# ResistorPatch1.net
KiCad netlist of a schematic drawn in Altium Designer
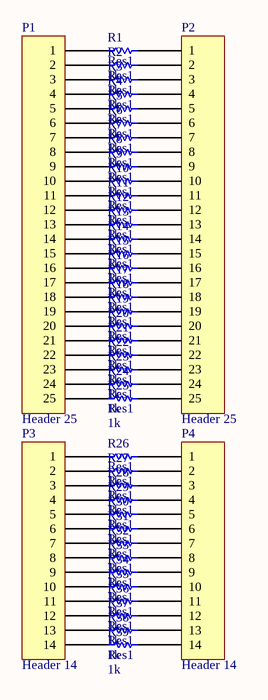
[diagram p0: ResistorPatch1.SchDoc]

(export (version "E")
  (design (tool "Eeschema 10.0.6"))
  (components
    (comp (ref "P1")
      (value "Header 25")
      (footprint "HDR1X25")
      (description "Header, 25-Pin")
      (fields (field (name "PUBLISHER") "Altium Limited"))
      (libsource (lib "") (part "Header 25_1"))
    )
    (comp (ref "P2")
      (value "Header 25")
      (footprint "HDR1X25H")
      (description "Header, 25-Pin")
      (fields (field (name "PUBLISHER") "Altium Limited"))
      (libsource (lib "Miscellaneous Connectors") (part "Header 25"))
    )
    (comp (ref "P3")
      (value "Header 14")
      (footprint "HDR1X14")
      (description "Header, 14-Pin")
      (fields (field (name "PUBLISHER") "Altium Limited"))
      (libsource (lib "") (part "Header 14_1"))
    )
    (comp (ref "P4")
      (value "Header 14")
      (footprint "HDR1X14H")
      (description "Header, 14-Pin")
      (fields (field (name "PUBLISHER") "Altium Limited"))
      (libsource (lib "Miscellaneous Connectors") (part "Header 14"))
    )
    (comp (ref "R1")
      (value "Res1")
      (footprint "AXIAL-0.4")
      (description "Resistor")
      (fields (field (name "ALTIUM_VALUE") "1k") (field (name "PUBLISHER") "Altium Limited"))
      (libsource (lib "Miscellaneous Devices") (part "Res1"))
    )
    (comp (ref "R2")
      (value "Res1")
      (footprint "AXIAL-0.4")
      (description "Resistor")
      (fields (field (name "ALTIUM_VALUE") "1k") (field (name "PUBLISHER") "Altium Limited"))
      (libsource (lib "Miscellaneous Devices") (part "Res1"))
    )
    (comp (ref "R3")
      (value "Res1")
      (footprint "AXIAL-0.4")
      (description "Resistor")
      (fields (field (name "ALTIUM_VALUE") "1k") (field (name "PUBLISHER") "Altium Limited"))
      (libsource (lib "Miscellaneous Devices") (part "Res1"))
    )
    (comp (ref "R4")
      (value "Res1")
      (footprint "AXIAL-0.4")
      (description "Resistor")
      (fields (field (name "ALTIUM_VALUE") "1k") (field (name "PUBLISHER") "Altium Limited"))
      (libsource (lib "Miscellaneous Devices") (part "Res1"))
    )
    (comp (ref "R5")
      (value "Res1")
      (footprint "AXIAL-0.4")
      (description "Resistor")
      (fields (field (name "ALTIUM_VALUE") "1k") (field (name "PUBLISHER") "Altium Limited"))
      (libsource (lib "Miscellaneous Devices") (part "Res1"))
    )
    (comp (ref "R6")
      (value "Res1")
      (footprint "AXIAL-0.4")
      (description "Resistor")
      (fields (field (name "ALTIUM_VALUE") "1k") (field (name "PUBLISHER") "Altium Limited"))
      (libsource (lib "Miscellaneous Devices") (part "Res1"))
    )
    (comp (ref "R7")
      (value "Res1")
      (footprint "AXIAL-0.4")
      (description "Resistor")
      (fields (field (name "ALTIUM_VALUE") "1k") (field (name "PUBLISHER") "Altium Limited"))
      (libsource (lib "Miscellaneous Devices") (part "Res1"))
    )
    (comp (ref "R8")
      (value "Res1")
      (footprint "AXIAL-0.4")
      (description "Resistor")
      (fields (field (name "ALTIUM_VALUE") "1k") (field (name "PUBLISHER") "Altium Limited"))
      (libsource (lib "Miscellaneous Devices") (part "Res1"))
    )
    (comp (ref "R9")
      (value "Res1")
      (footprint "AXIAL-0.4")
      (description "Resistor")
      (fields (field (name "ALTIUM_VALUE") "1k") (field (name "PUBLISHER") "Altium Limited"))
      (libsource (lib "Miscellaneous Devices") (part "Res1"))
    )
    (comp (ref "R10")
      (value "Res1")
      (footprint "AXIAL-0.4")
      (description "Resistor")
      (fields (field (name "ALTIUM_VALUE") "1k") (field (name "PUBLISHER") "Altium Limited"))
      (libsource (lib "Miscellaneous Devices") (part "Res1"))
    )
    (comp (ref "R11")
      (value "Res1")
      (footprint "AXIAL-0.4")
      (description "Resistor")
      (fields (field (name "ALTIUM_VALUE") "1k") (field (name "PUBLISHER") "Altium Limited"))
      (libsource (lib "Miscellaneous Devices") (part "Res1"))
    )
    (comp (ref "R12")
      (value "Res1")
      (footprint "AXIAL-0.4")
      (description "Resistor")
      (fields (field (name "ALTIUM_VALUE") "1k") (field (name "PUBLISHER") "Altium Limited"))
      (libsource (lib "Miscellaneous Devices") (part "Res1"))
    )
    (comp (ref "R13")
      (value "Res1")
      (footprint "AXIAL-0.4")
      (description "Resistor")
      (fields (field (name "ALTIUM_VALUE") "1k") (field (name "PUBLISHER") "Altium Limited"))
      (libsource (lib "Miscellaneous Devices") (part "Res1"))
    )
    (comp (ref "R14")
      (value "Res1")
      (footprint "AXIAL-0.4")
      (description "Resistor")
      (fields (field (name "ALTIUM_VALUE") "1k") (field (name "PUBLISHER") "Altium Limited"))
      (libsource (lib "Miscellaneous Devices") (part "Res1"))
    )
    (comp (ref "R15")
      (value "Res1")
      (footprint "AXIAL-0.4")
      (description "Resistor")
      (fields (field (name "ALTIUM_VALUE") "1k") (field (name "PUBLISHER") "Altium Limited"))
      (libsource (lib "Miscellaneous Devices") (part "Res1"))
    )
    (comp (ref "R16")
      (value "Res1")
      (footprint "AXIAL-0.4")
      (description "Resistor")
      (fields (field (name "ALTIUM_VALUE") "1k") (field (name "PUBLISHER") "Altium Limited"))
      (libsource (lib "Miscellaneous Devices") (part "Res1"))
    )
    (comp (ref "R17")
      (value "Res1")
      (footprint "AXIAL-0.4")
      (description "Resistor")
      (fields (field (name "ALTIUM_VALUE") "1k") (field (name "PUBLISHER") "Altium Limited"))
      (libsource (lib "Miscellaneous Devices") (part "Res1"))
    )
    (comp (ref "R18")
      (value "Res1")
      (footprint "AXIAL-0.4")
      (description "Resistor")
      (fields (field (name "ALTIUM_VALUE") "1k") (field (name "PUBLISHER") "Altium Limited"))
      (libsource (lib "Miscellaneous Devices") (part "Res1"))
    )
    (comp (ref "R19")
      (value "Res1")
      (footprint "AXIAL-0.4")
      (description "Resistor")
      (fields (field (name "ALTIUM_VALUE") "1k") (field (name "PUBLISHER") "Altium Limited"))
      (libsource (lib "Miscellaneous Devices") (part "Res1"))
    )
    (comp (ref "R20")
      (value "Res1")
      (footprint "AXIAL-0.4")
      (description "Resistor")
      (fields (field (name "ALTIUM_VALUE") "1k") (field (name "PUBLISHER") "Altium Limited"))
      (libsource (lib "Miscellaneous Devices") (part "Res1"))
    )
    (comp (ref "R21")
      (value "Res1")
      (footprint "AXIAL-0.4")
      (description "Resistor")
      (fields (field (name "ALTIUM_VALUE") "1k") (field (name "PUBLISHER") "Altium Limited"))
      (libsource (lib "Miscellaneous Devices") (part "Res1"))
    )
    (comp (ref "R22")
      (value "Res1")
      (footprint "AXIAL-0.4")
      (description "Resistor")
      (fields (field (name "ALTIUM_VALUE") "1k") (field (name "PUBLISHER") "Altium Limited"))
      (libsource (lib "Miscellaneous Devices") (part "Res1"))
    )
    (comp (ref "R23")
      (value "Res1")
      (footprint "AXIAL-0.4")
      (description "Resistor")
      (fields (field (name "ALTIUM_VALUE") "1k") (field (name "PUBLISHER") "Altium Limited"))
      (libsource (lib "Miscellaneous Devices") (part "Res1"))
    )
    (comp (ref "R24")
      (value "Res1")
      (footprint "AXIAL-0.4")
      (description "Resistor")
      (fields (field (name "ALTIUM_VALUE") "1k") (field (name "PUBLISHER") "Altium Limited"))
      (libsource (lib "Miscellaneous Devices") (part "Res1"))
    )
    (comp (ref "R25")
      (value "Res1")
      (footprint "AXIAL-0.4")
      (description "Resistor")
      (fields (field (name "ALTIUM_VALUE") "1k") (field (name "PUBLISHER") "Altium Limited"))
      (libsource (lib "Miscellaneous Devices") (part "Res1"))
    )
    (comp (ref "R26")
      (value "Res1")
      (footprint "AXIAL-0.4")
      (description "Resistor")
      (fields (field (name "ALTIUM_VALUE") "1k") (field (name "PUBLISHER") "Altium Limited"))
      (libsource (lib "Miscellaneous Devices") (part "Res1"))
    )
    (comp (ref "R27")
      (value "Res1")
      (footprint "AXIAL-0.4")
      (description "Resistor")
      (fields (field (name "ALTIUM_VALUE") "1k") (field (name "PUBLISHER") "Altium Limited"))
      (libsource (lib "Miscellaneous Devices") (part "Res1"))
    )
    (comp (ref "R28")
      (value "Res1")
      (footprint "AXIAL-0.4")
      (description "Resistor")
      (fields (field (name "ALTIUM_VALUE") "1k") (field (name "PUBLISHER") "Altium Limited"))
      (libsource (lib "Miscellaneous Devices") (part "Res1"))
    )
    (comp (ref "R29")
      (value "Res1")
      (footprint "AXIAL-0.4")
      (description "Resistor")
      (fields (field (name "ALTIUM_VALUE") "1k") (field (name "PUBLISHER") "Altium Limited"))
      (libsource (lib "Miscellaneous Devices") (part "Res1"))
    )
    (comp (ref "R30")
      (value "Res1")
      (footprint "AXIAL-0.4")
      (description "Resistor")
      (fields (field (name "ALTIUM_VALUE") "1k") (field (name "PUBLISHER") "Altium Limited"))
      (libsource (lib "Miscellaneous Devices") (part "Res1"))
    )
    (comp (ref "R31")
      (value "Res1")
      (footprint "AXIAL-0.4")
      (description "Resistor")
      (fields (field (name "ALTIUM_VALUE") "1k") (field (name "PUBLISHER") "Altium Limited"))
      (libsource (lib "Miscellaneous Devices") (part "Res1"))
    )
    (comp (ref "R32")
      (value "Res1")
      (footprint "AXIAL-0.4")
      (description "Resistor")
      (fields (field (name "ALTIUM_VALUE") "1k") (field (name "PUBLISHER") "Altium Limited"))
      (libsource (lib "Miscellaneous Devices") (part "Res1"))
    )
    (comp (ref "R33")
      (value "Res1")
      (footprint "AXIAL-0.4")
      (description "Resistor")
      (fields (field (name "ALTIUM_VALUE") "1k") (field (name "PUBLISHER") "Altium Limited"))
      (libsource (lib "Miscellaneous Devices") (part "Res1"))
    )
    (comp (ref "R34")
      (value "Res1")
      (footprint "AXIAL-0.4")
      (description "Resistor")
      (fields (field (name "ALTIUM_VALUE") "1k") (field (name "PUBLISHER") "Altium Limited"))
      (libsource (lib "Miscellaneous Devices") (part "Res1"))
    )
    (comp (ref "R35")
      (value "Res1")
      (footprint "AXIAL-0.4")
      (description "Resistor")
      (fields (field (name "ALTIUM_VALUE") "1k") (field (name "PUBLISHER") "Altium Limited"))
      (libsource (lib "Miscellaneous Devices") (part "Res1"))
    )
    (comp (ref "R36")
      (value "Res1")
      (footprint "AXIAL-0.4")
      (description "Resistor")
      (fields (field (name "ALTIUM_VALUE") "1k") (field (name "PUBLISHER") "Altium Limited"))
      (libsource (lib "Miscellaneous Devices") (part "Res1"))
    )
    (comp (ref "R37")
      (value "Res1")
      (footprint "AXIAL-0.4")
      (description "Resistor")
      (fields (field (name "ALTIUM_VALUE") "1k") (field (name "PUBLISHER") "Altium Limited"))
      (libsource (lib "Miscellaneous Devices") (part "Res1"))
    )
    (comp (ref "R38")
      (value "Res1")
      (footprint "AXIAL-0.4")
      (description "Resistor")
      (fields (field (name "ALTIUM_VALUE") "1k") (field (name "PUBLISHER") "Altium Limited"))
      (libsource (lib "Miscellaneous Devices") (part "Res1"))
    )
    (comp (ref "R39")
      (value "Res1")
      (footprint "AXIAL-0.4")
      (description "Resistor")
      (fields (field (name "ALTIUM_VALUE") "1k") (field (name "PUBLISHER") "Altium Limited"))
      (libsource (lib "Miscellaneous Devices") (part "Res1"))
    )
  )
  (nets
    (net (code "1") (name "Net-(P1-Pad1)") (class "Default")
      (node (ref "P1") (pin "1") (pinfunction "1_1") (pintype "passive"))
      (node (ref "R1") (pin "1") (pinfunction "1_1") (pintype "passive"))
    )
    (net (code "2") (name "Net-(P1-Pad2)") (class "Default")
      (node (ref "P1") (pin "2") (pinfunction "2_2") (pintype "passive"))
      (node (ref "R2") (pin "1") (pinfunction "1_1") (pintype "passive"))
    )
    (net (code "3") (name "Net-(P1-Pad3)") (class "Default")
      (node (ref "P1") (pin "3") (pinfunction "3_3") (pintype "passive"))
      (node (ref "R3") (pin "1") (pinfunction "1_1") (pintype "passive"))
    )
    (net (code "4") (name "Net-(P1-Pad4)") (class "Default")
      (node (ref "P1") (pin "4") (pinfunction "4_4") (pintype "passive"))
      (node (ref "R4") (pin "1") (pinfunction "1_1") (pintype "passive"))
    )
    (net (code "5") (name "Net-(P1-Pad5)") (class "Default")
      (node (ref "P1") (pin "5") (pinfunction "5_5") (pintype "passive"))
      (node (ref "R5") (pin "1") (pinfunction "1_1") (pintype "passive"))
    )
    (net (code "6") (name "Net-(P1-Pad6)") (class "Default")
      (node (ref "P1") (pin "6") (pinfunction "6_6") (pintype "passive"))
      (node (ref "R6") (pin "1") (pinfunction "1_1") (pintype "passive"))
    )
    (net (code "7") (name "Net-(P1-Pad7)") (class "Default")
      (node (ref "P1") (pin "7") (pinfunction "7_7") (pintype "passive"))
      (node (ref "R7") (pin "1") (pinfunction "1_1") (pintype "passive"))
    )
    (net (code "8") (name "Net-(P1-Pad8)") (class "Default")
      (node (ref "P1") (pin "8") (pinfunction "8_8") (pintype "passive"))
      (node (ref "R8") (pin "1") (pinfunction "1_1") (pintype "passive"))
    )
    (net (code "9") (name "Net-(P1-Pad9)") (class "Default")
      (node (ref "P1") (pin "9") (pinfunction "9_9") (pintype "passive"))
      (node (ref "R9") (pin "1") (pinfunction "1_1") (pintype "passive"))
    )
    (net (code "10") (name "Net-(P1-Pad10)") (class "Default")
      (node (ref "P1") (pin "10") (pinfunction "10_10") (pintype "passive"))
      (node (ref "R10") (pin "1") (pinfunction "1_1") (pintype "passive"))
    )
    (net (code "11") (name "Net-(P1-Pad11)") (class "Default")
      (node (ref "P1") (pin "11") (pinfunction "11_11") (pintype "passive"))
      (node (ref "R11") (pin "1") (pinfunction "1_1") (pintype "passive"))
    )
    (net (code "12") (name "Net-(P1-Pad12)") (class "Default")
      (node (ref "P1") (pin "12") (pinfunction "12_12") (pintype "passive"))
      (node (ref "R12") (pin "1") (pinfunction "1_1") (pintype "passive"))
    )
    (net (code "13") (name "Net-(P1-Pad13)") (class "Default")
      (node (ref "P1") (pin "13") (pinfunction "13_13") (pintype "passive"))
      (node (ref "R13") (pin "1") (pinfunction "1_1") (pintype "passive"))
    )
    (net (code "14") (name "Net-(P1-Pad14)") (class "Default")
      (node (ref "P1") (pin "14") (pinfunction "14_14") (pintype "passive"))
      (node (ref "R14") (pin "1") (pinfunction "1_1") (pintype "passive"))
    )
    (net (code "15") (name "Net-(P1-Pad15)") (class "Default")
      (node (ref "P1") (pin "15") (pinfunction "15_15") (pintype "passive"))
      (node (ref "R15") (pin "1") (pinfunction "1_1") (pintype "passive"))
    )
    (net (code "16") (name "Net-(P1-Pad16)") (class "Default")
      (node (ref "P1") (pin "16") (pinfunction "16_16") (pintype "passive"))
      (node (ref "R16") (pin "1") (pinfunction "1_1") (pintype "passive"))
    )
    (net (code "17") (name "Net-(P1-Pad17)") (class "Default")
      (node (ref "P1") (pin "17") (pinfunction "17_17") (pintype "passive"))
      (node (ref "R17") (pin "1") (pinfunction "1_1") (pintype "passive"))
    )
    (net (code "18") (name "Net-(P1-Pad18)") (class "Default")
      (node (ref "P1") (pin "18") (pinfunction "18_18") (pintype "passive"))
      (node (ref "R18") (pin "1") (pinfunction "1_1") (pintype "passive"))
    )
    (net (code "19") (name "Net-(P1-Pad19)") (class "Default")
      (node (ref "P1") (pin "19") (pinfunction "19_19") (pintype "passive"))
      (node (ref "R19") (pin "1") (pinfunction "1_1") (pintype "passive"))
    )
    (net (code "20") (name "Net-(P1-Pad20)") (class "Default")
      (node (ref "P1") (pin "20") (pinfunction "20_20") (pintype "passive"))
      (node (ref "R20") (pin "1") (pinfunction "1_1") (pintype "passive"))
    )
    (net (code "21") (name "Net-(P1-Pad21)") (class "Default")
      (node (ref "P1") (pin "21") (pinfunction "21_21") (pintype "passive"))
      (node (ref "R21") (pin "1") (pinfunction "1_1") (pintype "passive"))
    )
    (net (code "22") (name "Net-(P1-Pad22)") (class "Default")
      (node (ref "P1") (pin "22") (pinfunction "22_22") (pintype "passive"))
      (node (ref "R22") (pin "1") (pinfunction "1_1") (pintype "passive"))
    )
    (net (code "23") (name "Net-(P1-Pad23)") (class "Default")
      (node (ref "P1") (pin "23") (pinfunction "23_23") (pintype "passive"))
      (node (ref "R23") (pin "1") (pinfunction "1_1") (pintype "passive"))
    )
    (net (code "24") (name "Net-(P1-Pad24)") (class "Default")
      (node (ref "P1") (pin "24") (pinfunction "24_24") (pintype "passive"))
      (node (ref "R24") (pin "1") (pinfunction "1_1") (pintype "passive"))
    )
    (net (code "25") (name "Net-(P1-Pad25)") (class "Default")
      (node (ref "P1") (pin "25") (pinfunction "25_25") (pintype "passive"))
      (node (ref "R25") (pin "1") (pinfunction "1_1") (pintype "passive"))
    )
    (net (code "26") (name "Net-(P2-Pad1)") (class "Default")
      (node (ref "P2") (pin "1") (pinfunction "1_1") (pintype "passive"))
      (node (ref "R1") (pin "2") (pinfunction "2_2") (pintype "passive"))
    )
    (net (code "27") (name "Net-(P2-Pad2)") (class "Default")
      (node (ref "P2") (pin "2") (pinfunction "2_2") (pintype "passive"))
      (node (ref "R2") (pin "2") (pinfunction "2_2") (pintype "passive"))
    )
    (net (code "28") (name "Net-(P2-Pad3)") (class "Default")
      (node (ref "P2") (pin "3") (pinfunction "3_3") (pintype "passive"))
      (node (ref "R3") (pin "2") (pinfunction "2_2") (pintype "passive"))
    )
    (net (code "29") (name "Net-(P2-Pad4)") (class "Default")
      (node (ref "P2") (pin "4") (pinfunction "4_4") (pintype "passive"))
      (node (ref "R4") (pin "2") (pinfunction "2_2") (pintype "passive"))
    )
    (net (code "30") (name "Net-(P2-Pad5)") (class "Default")
      (node (ref "P2") (pin "5") (pinfunction "5_5") (pintype "passive"))
      (node (ref "R5") (pin "2") (pinfunction "2_2") (pintype "passive"))
    )
    (net (code "31") (name "Net-(P2-Pad6)") (class "Default")
      (node (ref "P2") (pin "6") (pinfunction "6_6") (pintype "passive"))
      (node (ref "R6") (pin "2") (pinfunction "2_2") (pintype "passive"))
    )
    (net (code "32") (name "Net-(P2-Pad7)") (class "Default")
      (node (ref "P2") (pin "7") (pinfunction "7_7") (pintype "passive"))
      (node (ref "R7") (pin "2") (pinfunction "2_2") (pintype "passive"))
    )
    (net (code "33") (name "Net-(P2-Pad8)") (class "Default")
      (node (ref "P2") (pin "8") (pinfunction "8_8") (pintype "passive"))
      (node (ref "R8") (pin "2") (pinfunction "2_2") (pintype "passive"))
    )
    (net (code "34") (name "Net-(P2-Pad9)") (class "Default")
      (node (ref "P2") (pin "9") (pinfunction "9_9") (pintype "passive"))
      (node (ref "R9") (pin "2") (pinfunction "2_2") (pintype "passive"))
    )
    (net (code "35") (name "Net-(P2-Pad10)") (class "Default")
      (node (ref "P2") (pin "10") (pinfunction "10_10") (pintype "passive"))
      (node (ref "R10") (pin "2") (pinfunction "2_2") (pintype "passive"))
    )
    (net (code "36") (name "Net-(P2-Pad11)") (class "Default")
      (node (ref "P2") (pin "11") (pinfunction "11_11") (pintype "passive"))
      (node (ref "R11") (pin "2") (pinfunction "2_2") (pintype "passive"))
    )
    (net (code "37") (name "Net-(P2-Pad12)") (class "Default")
      (node (ref "P2") (pin "12") (pinfunction "12_12") (pintype "passive"))
      (node (ref "R12") (pin "2") (pinfunction "2_2") (pintype "passive"))
    )
    (net (code "38") (name "Net-(P2-Pad13)") (class "Default")
      (node (ref "P2") (pin "13") (pinfunction "13_13") (pintype "passive"))
      (node (ref "R13") (pin "2") (pinfunction "2_2") (pintype "passive"))
    )
    (net (code "39") (name "Net-(P2-Pad14)") (class "Default")
      (node (ref "P2") (pin "14") (pinfunction "14_14") (pintype "passive"))
      (node (ref "R14") (pin "2") (pinfunction "2_2") (pintype "passive"))
    )
    (net (code "40") (name "Net-(P2-Pad15)") (class "Default")
      (node (ref "P2") (pin "15") (pinfunction "15_15") (pintype "passive"))
      (node (ref "R15") (pin "2") (pinfunction "2_2") (pintype "passive"))
    )
    (net (code "41") (name "Net-(P2-Pad16)") (class "Default")
      (node (ref "P2") (pin "16") (pinfunction "16_16") (pintype "passive"))
      (node (ref "R16") (pin "2") (pinfunction "2_2") (pintype "passive"))
    )
    (net (code "42") (name "Net-(P2-Pad17)") (class "Default")
      (node (ref "P2") (pin "17") (pinfunction "17_17") (pintype "passive"))
      (node (ref "R17") (pin "2") (pinfunction "2_2") (pintype "passive"))
    )
    (net (code "43") (name "Net-(P2-Pad18)") (class "Default")
      (node (ref "P2") (pin "18") (pinfunction "18_18") (pintype "passive"))
      (node (ref "R18") (pin "2") (pinfunction "2_2") (pintype "passive"))
    )
    (net (code "44") (name "Net-(P2-Pad19)") (class "Default")
      (node (ref "P2") (pin "19") (pinfunction "19_19") (pintype "passive"))
      (node (ref "R19") (pin "2") (pinfunction "2_2") (pintype "passive"))
    )
    (net (code "45") (name "Net-(P2-Pad20)") (class "Default")
      (node (ref "P2") (pin "20") (pinfunction "20_20") (pintype "passive"))
      (node (ref "R20") (pin "2") (pinfunction "2_2") (pintype "passive"))
    )
    (net (code "46") (name "Net-(P2-Pad21)") (class "Default")
      (node (ref "P2") (pin "21") (pinfunction "21_21") (pintype "passive"))
      (node (ref "R21") (pin "2") (pinfunction "2_2") (pintype "passive"))
    )
    (net (code "47") (name "Net-(P2-Pad22)") (class "Default")
      (node (ref "P2") (pin "22") (pinfunction "22_22") (pintype "passive"))
      (node (ref "R22") (pin "2") (pinfunction "2_2") (pintype "passive"))
    )
    (net (code "48") (name "Net-(P2-Pad23)") (class "Default")
      (node (ref "P2") (pin "23") (pinfunction "23_23") (pintype "passive"))
      (node (ref "R23") (pin "2") (pinfunction "2_2") (pintype "passive"))
    )
    (net (code "49") (name "Net-(P2-Pad24)") (class "Default")
      (node (ref "P2") (pin "24") (pinfunction "24_24") (pintype "passive"))
      (node (ref "R24") (pin "2") (pinfunction "2_2") (pintype "passive"))
    )
    (net (code "50") (name "Net-(P2-Pad25)") (class "Default")
      (node (ref "P2") (pin "25") (pinfunction "25_25") (pintype "passive"))
      (node (ref "R25") (pin "2") (pinfunction "2_2") (pintype "passive"))
    )
    (net (code "51") (name "Net-(P3-Pad1)") (class "Default")
      (node (ref "P3") (pin "1") (pinfunction "1_1") (pintype "passive"))
      (node (ref "R26") (pin "1") (pinfunction "1_1") (pintype "passive"))
    )
    (net (code "52") (name "Net-(P3-Pad2)") (class "Default")
      (node (ref "P3") (pin "2") (pinfunction "2_2") (pintype "passive"))
      (node (ref "R27") (pin "1") (pinfunction "1_1") (pintype "passive"))
    )
    (net (code "53") (name "Net-(P3-Pad3)") (class "Default")
      (node (ref "P3") (pin "3") (pinfunction "3_3") (pintype "passive"))
      (node (ref "R28") (pin "1") (pinfunction "1_1") (pintype "passive"))
    )
    (net (code "54") (name "Net-(P3-Pad4)") (class "Default")
      (node (ref "P3") (pin "4") (pinfunction "4_4") (pintype "passive"))
      (node (ref "R29") (pin "1") (pinfunction "1_1") (pintype "passive"))
    )
    (net (code "55") (name "Net-(P3-Pad5)") (class "Default")
      (node (ref "P3") (pin "5") (pinfunction "5_5") (pintype "passive"))
      (node (ref "R30") (pin "1") (pinfunction "1_1") (pintype "passive"))
    )
    (net (code "56") (name "Net-(P3-Pad6)") (class "Default")
      (node (ref "P3") (pin "6") (pinfunction "6_6") (pintype "passive"))
      (node (ref "R31") (pin "1") (pinfunction "1_1") (pintype "passive"))
    )
    (net (code "57") (name "Net-(P3-Pad7)") (class "Default")
      (node (ref "P3") (pin "7") (pinfunction "7_7") (pintype "passive"))
      (node (ref "R32") (pin "1") (pinfunction "1_1") (pintype "passive"))
    )
    (net (code "58") (name "Net-(P3-Pad8)") (class "Default")
      (node (ref "P3") (pin "8") (pinfunction "8_8") (pintype "passive"))
      (node (ref "R33") (pin "1") (pinfunction "1_1") (pintype "passive"))
    )
    (net (code "59") (name "Net-(P3-Pad9)") (class "Default")
      (node (ref "P3") (pin "9") (pinfunction "9_9") (pintype "passive"))
      (node (ref "R34") (pin "1") (pinfunction "1_1") (pintype "passive"))
    )
    (net (code "60") (name "Net-(P3-Pad10)") (class "Default")
      (node (ref "P3") (pin "10") (pinfunction "10_10") (pintype "passive"))
      (node (ref "R35") (pin "1") (pinfunction "1_1") (pintype "passive"))
    )
    (net (code "61") (name "Net-(P3-Pad11)") (class "Default")
      (node (ref "P3") (pin "11") (pinfunction "11_11") (pintype "passive"))
      (node (ref "R36") (pin "1") (pinfunction "1_1") (pintype "passive"))
    )
    (net (code "62") (name "Net-(P3-Pad12)") (class "Default")
      (node (ref "P3") (pin "12") (pinfunction "12_12") (pintype "passive"))
      (node (ref "R37") (pin "1") (pinfunction "1_1") (pintype "passive"))
    )
    (net (code "63") (name "Net-(P3-Pad13)") (class "Default")
      (node (ref "P3") (pin "13") (pinfunction "13_13") (pintype "passive"))
      (node (ref "R38") (pin "1") (pinfunction "1_1") (pintype "passive"))
    )
    (net (code "64") (name "Net-(P3-Pad14)") (class "Default")
      (node (ref "P3") (pin "14") (pinfunction "14_14") (pintype "passive"))
      (node (ref "R39") (pin "1") (pinfunction "1_1") (pintype "passive"))
    )
    (net (code "65") (name "Net-(P4-Pad1)") (class "Default")
      (node (ref "P4") (pin "1") (pinfunction "1_1") (pintype "passive"))
      (node (ref "R26") (pin "2") (pinfunction "2_2") (pintype "passive"))
    )
    (net (code "66") (name "Net-(P4-Pad2)") (class "Default")
      (node (ref "P4") (pin "2") (pinfunction "2_2") (pintype "passive"))
      (node (ref "R27") (pin "2") (pinfunction "2_2") (pintype "passive"))
    )
    (net (code "67") (name "Net-(P4-Pad3)") (class "Default")
      (node (ref "P4") (pin "3") (pinfunction "3_3") (pintype "passive"))
      (node (ref "R28") (pin "2") (pinfunction "2_2") (pintype "passive"))
    )
    (net (code "68") (name "Net-(P4-Pad4)") (class "Default")
      (node (ref "P4") (pin "4") (pinfunction "4_4") (pintype "passive"))
      (node (ref "R29") (pin "2") (pinfunction "2_2") (pintype "passive"))
    )
    (net (code "69") (name "Net-(P4-Pad5)") (class "Default")
      (node (ref "P4") (pin "5") (pinfunction "5_5") (pintype "passive"))
      (node (ref "R30") (pin "2") (pinfunction "2_2") (pintype "passive"))
    )
    (net (code "70") (name "Net-(P4-Pad6)") (class "Default")
      (node (ref "P4") (pin "6") (pinfunction "6_6") (pintype "passive"))
      (node (ref "R31") (pin "2") (pinfunction "2_2") (pintype "passive"))
    )
    (net (code "71") (name "Net-(P4-Pad7)") (class "Default")
      (node (ref "P4") (pin "7") (pinfunction "7_7") (pintype "passive"))
      (node (ref "R32") (pin "2") (pinfunction "2_2") (pintype "passive"))
    )
    (net (code "72") (name "Net-(P4-Pad8)") (class "Default")
      (node (ref "P4") (pin "8") (pinfunction "8_8") (pintype "passive"))
      (node (ref "R33") (pin "2") (pinfunction "2_2") (pintype "passive"))
    )
    (net (code "73") (name "Net-(P4-Pad9)") (class "Default")
      (node (ref "P4") (pin "9") (pinfunction "9_9") (pintype "passive"))
      (node (ref "R34") (pin "2") (pinfunction "2_2") (pintype "passive"))
    )
    (net (code "74") (name "Net-(P4-Pad10)") (class "Default")
      (node (ref "P4") (pin "10") (pinfunction "10_10") (pintype "passive"))
      (node (ref "R35") (pin "2") (pinfunction "2_2") (pintype "passive"))
    )
    (net (code "75") (name "Net-(P4-Pad11)") (class "Default")
      (node (ref "P4") (pin "11") (pinfunction "11_11") (pintype "passive"))
      (node (ref "R36") (pin "2") (pinfunction "2_2") (pintype "passive"))
    )
    (net (code "76") (name "Net-(P4-Pad12)") (class "Default")
      (node (ref "P4") (pin "12") (pinfunction "12_12") (pintype "passive"))
      (node (ref "R37") (pin "2") (pinfunction "2_2") (pintype "passive"))
    )
    (net (code "77") (name "Net-(P4-Pad13)") (class "Default")
      (node (ref "P4") (pin "13") (pinfunction "13_13") (pintype "passive"))
      (node (ref "R38") (pin "2") (pinfunction "2_2") (pintype "passive"))
    )
    (net (code "78") (name "Net-(P4-Pad14)") (class "Default")
      (node (ref "P4") (pin "14") (pinfunction "14_14") (pintype "passive"))
      (node (ref "R39") (pin "2") (pinfunction "2_2") (pintype "passive"))
    )
  )
)
